# IC_LPDDR4.net
KiCad netlist of a schematic drawn in Altium Designer
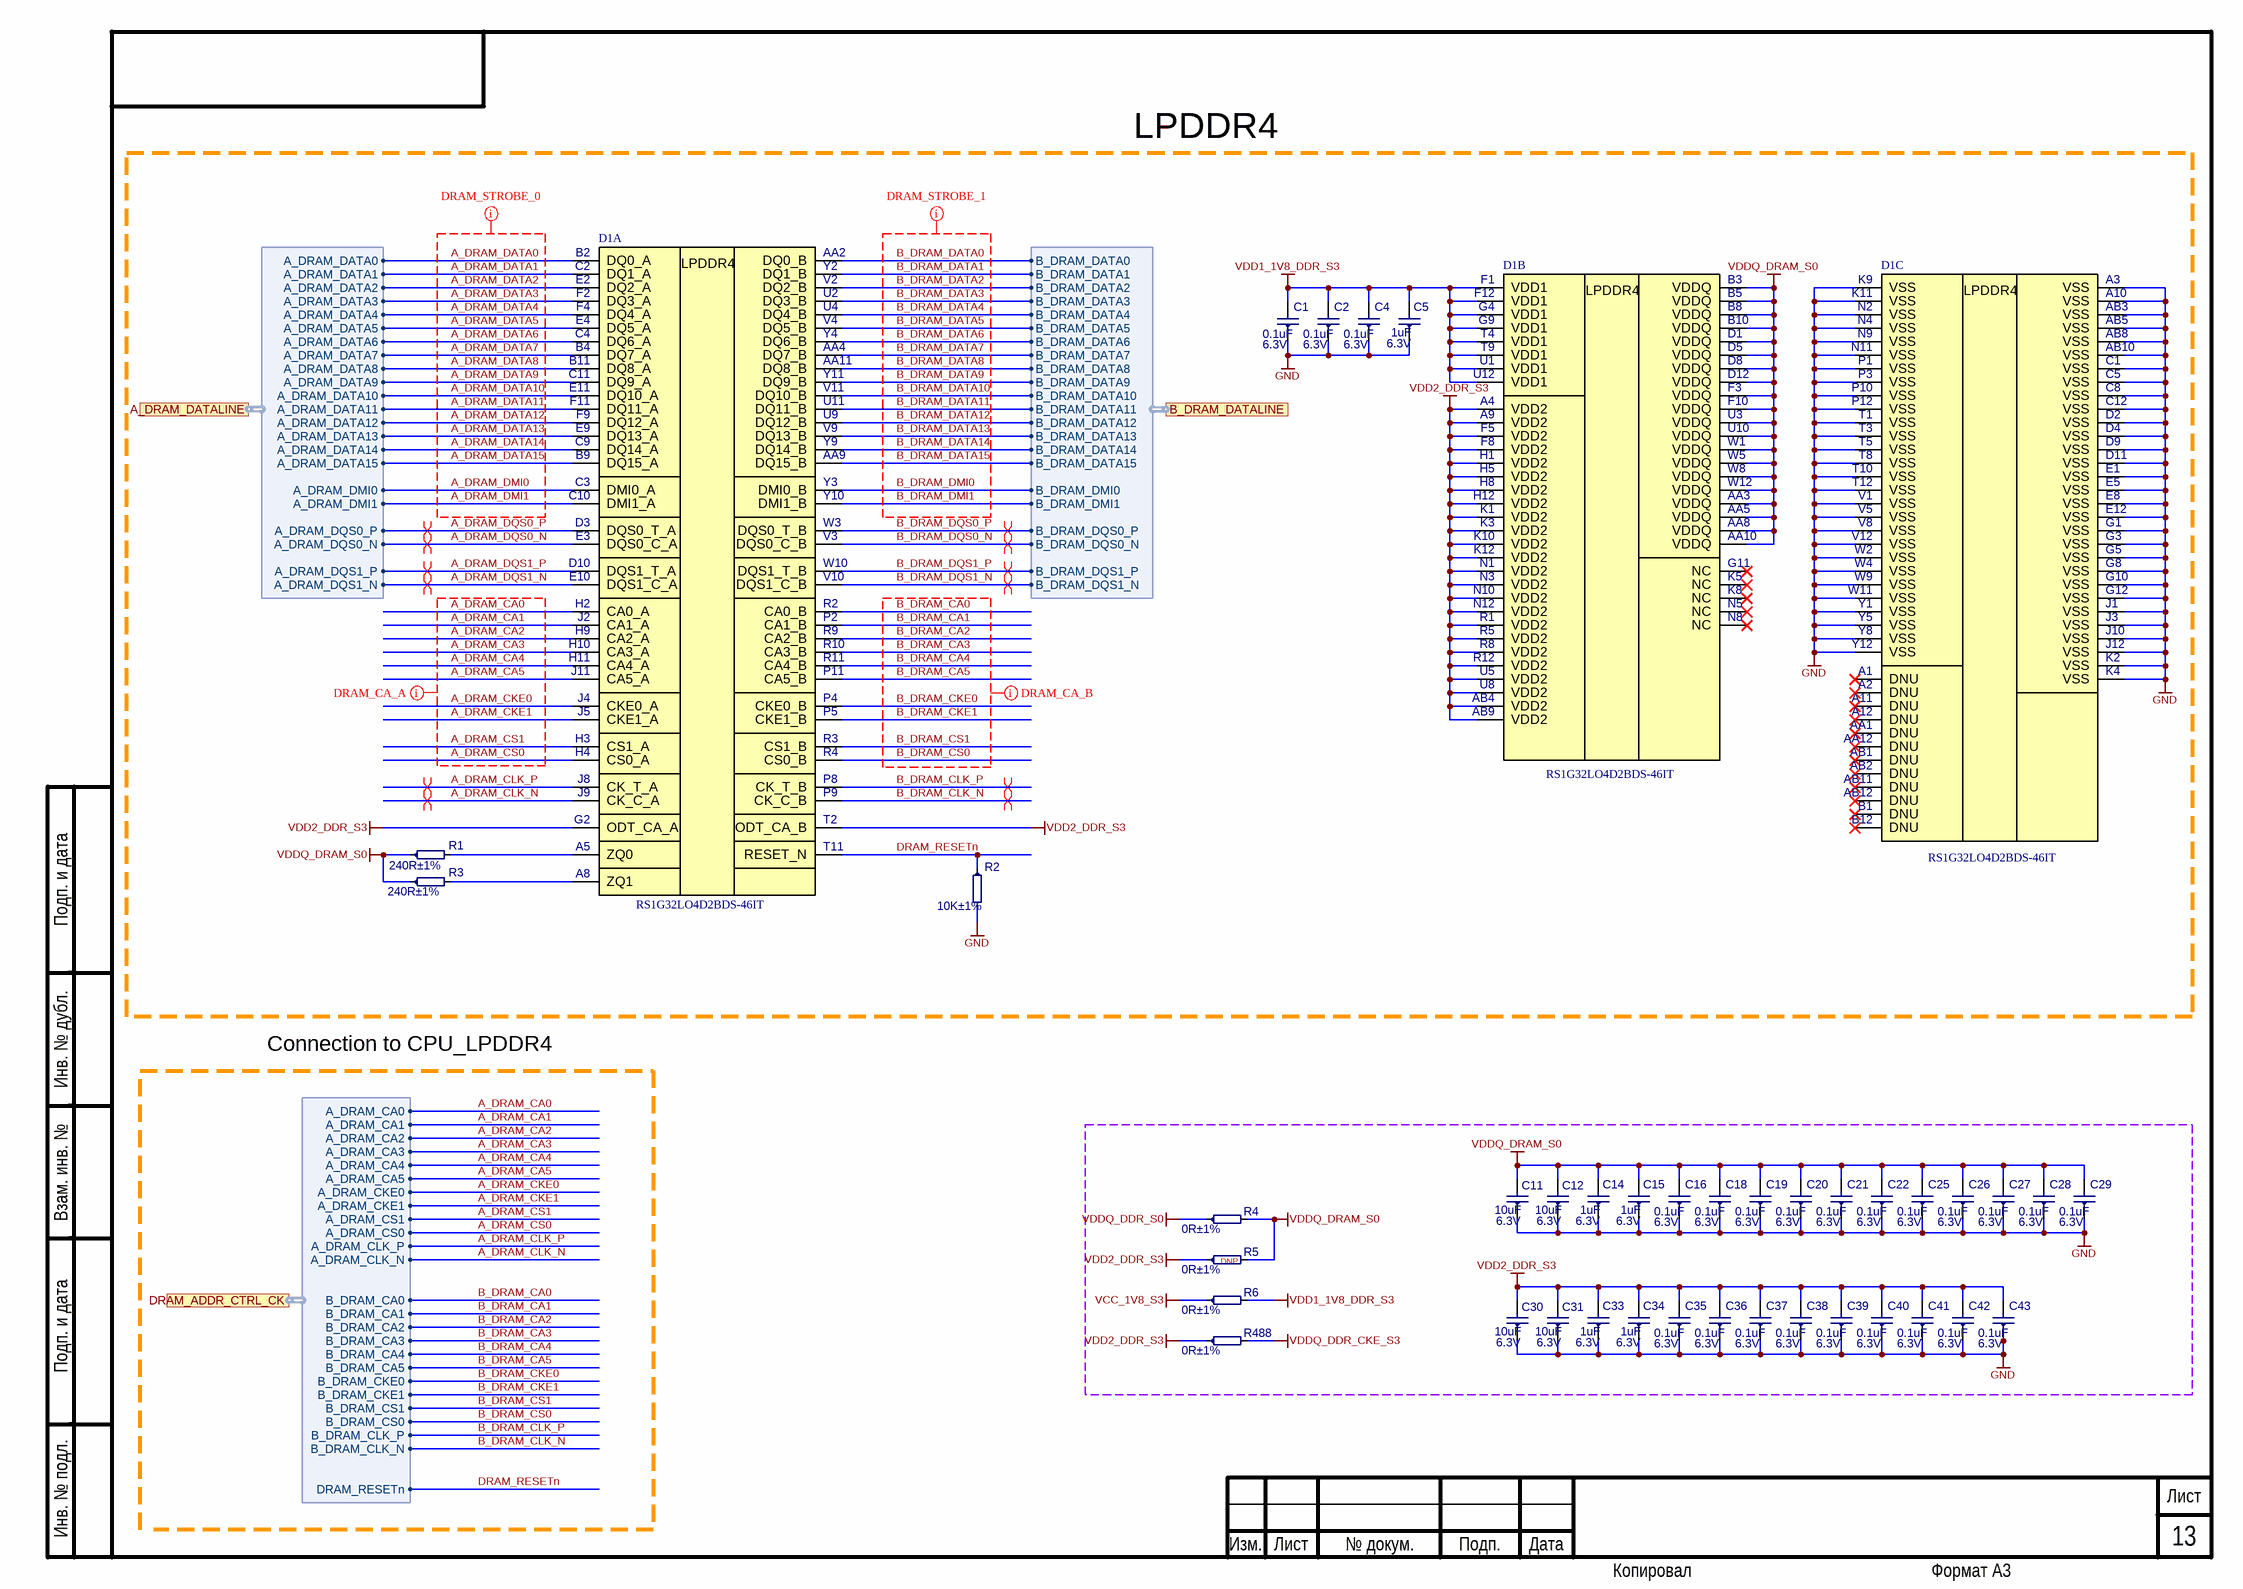
[diagram p0: IC_LPDDR4.SchDoc]

(export (version "E")
  (design (tool "Eeschema 10.0.6"))
  (components
    (comp (ref "C1")
      (value "0.1uF")
      (footprint "C0201")
      (fields
        (field (name "VOLTAGE") "6.3V")
        (field (name "PART NUMBER") "0201-X5R-6.3V-0.1uF±10%")
        (field (name "TOLERANCE") "10%")
        (field (name "MANUFACTURER") "Yageo")
      )
      (libsource (lib "ATB") (part "C"))
    )
    (comp (ref "C2")
      (value "0.1uF")
      (footprint "C0201")
      (fields
        (field (name "VOLTAGE") "6.3V")
        (field (name "PART NUMBER") "0201-X5R-6.3V-0.1uF±10%")
        (field (name "TOLERANCE") "10%")
        (field (name "MANUFACTURER") "Yageo")
      )
      (libsource (lib "ATB") (part "C"))
    )
    (comp (ref "C4")
      (value "0.1uF")
      (footprint "C0201")
      (fields
        (field (name "VOLTAGE") "6.3V")
        (field (name "PART NUMBER") "0201-X5R-6.3V-0.1uF±10%")
        (field (name "TOLERANCE") "10%")
        (field (name "MANUFACTURER") "Yageo")
      )
      (libsource (lib "ATB") (part "C"))
    )
    (comp (ref "C5")
      (value "1uF")
      (footprint "C0201")
      (fields
        (field (name "VOLTAGE") "6.3V")
        (field (name "PART NUMBER") "0201-X5R-6.3V-1uF±20%")
        (field (name "TOLERANCE") "20%")
        (field (name "MANUFACTURER") "Murata Electronics")
      )
      (libsource (lib "ATB") (part "C"))
    )
    (comp (ref "C11")
      (value "10uF")
      (footprint "C0402")
      (fields
        (field (name "VOLTAGE") "6.3V")
        (field (name "PART NUMBER") "0402-X5R-6.3V-10uF±20%")
        (field (name "TOLERANCE") "20%")
        (field (name "MANUFACTURER") "Yageo")
      )
      (libsource (lib "ATB") (part "C"))
    )
    (comp (ref "C12")
      (value "10uF")
      (footprint "C0402")
      (fields
        (field (name "VOLTAGE") "6.3V")
        (field (name "PART NUMBER") "0402-X5R-6.3V-10uF±20%")
        (field (name "TOLERANCE") "20%")
        (field (name "MANUFACTURER") "Yageo")
      )
      (libsource (lib "ATB") (part "C"))
    )
    (comp (ref "C14")
      (value "1uF")
      (footprint "C0201")
      (fields
        (field (name "VOLTAGE") "6.3V")
        (field (name "PART NUMBER") "0201-X5R-6.3V-1uF±20%")
        (field (name "TOLERANCE") "20%")
        (field (name "MANUFACTURER") "Murata Electronics")
      )
      (libsource (lib "ATB") (part "C"))
    )
    (comp (ref "C15")
      (value "1uF")
      (footprint "C0201")
      (fields
        (field (name "VOLTAGE") "6.3V")
        (field (name "PART NUMBER") "0201-X5R-6.3V-1uF±20%")
        (field (name "TOLERANCE") "20%")
        (field (name "MANUFACTURER") "Murata Electronics")
      )
      (libsource (lib "ATB") (part "C"))
    )
    (comp (ref "C16")
      (value "0.1uF")
      (footprint "C0201")
      (fields
        (field (name "VOLTAGE") "6.3V")
        (field (name "PART NUMBER") "0201-X5R-6.3V-0.1uF±10%")
        (field (name "TOLERANCE") "10%")
        (field (name "MANUFACTURER") "Yageo")
      )
      (libsource (lib "ATB") (part "C"))
    )
    (comp (ref "C18")
      (value "0.1uF")
      (footprint "C0201")
      (fields
        (field (name "VOLTAGE") "6.3V")
        (field (name "PART NUMBER") "0201-X5R-6.3V-0.1uF±10%")
        (field (name "TOLERANCE") "10%")
        (field (name "MANUFACTURER") "Yageo")
      )
      (libsource (lib "ATB") (part "C"))
    )
    (comp (ref "C19")
      (value "0.1uF")
      (footprint "C0201")
      (fields
        (field (name "VOLTAGE") "6.3V")
        (field (name "PART NUMBER") "0201-X5R-6.3V-0.1uF±10%")
        (field (name "TOLERANCE") "10%")
        (field (name "MANUFACTURER") "Yageo")
      )
      (libsource (lib "ATB") (part "C"))
    )
    (comp (ref "C20")
      (value "0.1uF")
      (footprint "C0201")
      (fields
        (field (name "VOLTAGE") "6.3V")
        (field (name "PART NUMBER") "0201-X5R-6.3V-0.1uF±10%")
        (field (name "TOLERANCE") "10%")
        (field (name "MANUFACTURER") "Yageo")
      )
      (libsource (lib "ATB") (part "C"))
    )
    (comp (ref "C21")
      (value "0.1uF")
      (footprint "C0201")
      (fields
        (field (name "VOLTAGE") "6.3V")
        (field (name "PART NUMBER") "0201-X5R-6.3V-0.1uF±10%")
        (field (name "TOLERANCE") "10%")
        (field (name "MANUFACTURER") "Yageo")
      )
      (libsource (lib "ATB") (part "C"))
    )
    (comp (ref "C22")
      (value "0.1uF")
      (footprint "C0201")
      (fields
        (field (name "VOLTAGE") "6.3V")
        (field (name "PART NUMBER") "0201-X5R-6.3V-0.1uF±10%")
        (field (name "TOLERANCE") "10%")
        (field (name "MANUFACTURER") "Yageo")
      )
      (libsource (lib "ATB") (part "C"))
    )
    (comp (ref "C25")
      (value "0.1uF")
      (footprint "C0201")
      (fields
        (field (name "VOLTAGE") "6.3V")
        (field (name "PART NUMBER") "0201-X5R-6.3V-0.1uF±10%")
        (field (name "TOLERANCE") "10%")
        (field (name "MANUFACTURER") "Yageo")
      )
      (libsource (lib "ATB") (part "C"))
    )
    (comp (ref "C26")
      (value "0.1uF")
      (footprint "C0201")
      (fields
        (field (name "VOLTAGE") "6.3V")
        (field (name "PART NUMBER") "0201-X5R-6.3V-0.1uF±10%")
        (field (name "TOLERANCE") "10%")
        (field (name "MANUFACTURER") "Yageo")
      )
      (libsource (lib "ATB") (part "C"))
    )
    (comp (ref "C27")
      (value "0.1uF")
      (footprint "C0201")
      (fields
        (field (name "VOLTAGE") "6.3V")
        (field (name "PART NUMBER") "0201-X5R-6.3V-0.1uF±10%")
        (field (name "TOLERANCE") "10%")
        (field (name "MANUFACTURER") "Yageo")
      )
      (libsource (lib "ATB") (part "C"))
    )
    (comp (ref "C28")
      (value "0.1uF")
      (footprint "C0201")
      (fields
        (field (name "VOLTAGE") "6.3V")
        (field (name "PART NUMBER") "0201-X5R-6.3V-0.1uF±10%")
        (field (name "TOLERANCE") "10%")
        (field (name "MANUFACTURER") "Yageo")
      )
      (libsource (lib "ATB") (part "C"))
    )
    (comp (ref "C29")
      (value "0.1uF")
      (footprint "C0201")
      (fields
        (field (name "VOLTAGE") "6.3V")
        (field (name "PART NUMBER") "0201-X5R-6.3V-0.1uF±10%")
        (field (name "TOLERANCE") "10%")
        (field (name "MANUFACTURER") "Yageo")
      )
      (libsource (lib "ATB") (part "C"))
    )
    (comp (ref "C30")
      (value "10uF")
      (footprint "C0402")
      (fields
        (field (name "VOLTAGE") "6.3V")
        (field (name "PART NUMBER") "0402-X5R-6.3V-10uF±20%")
        (field (name "TOLERANCE") "20%")
        (field (name "MANUFACTURER") "Yageo")
      )
      (libsource (lib "ATB") (part "C"))
    )
    (comp (ref "C31")
      (value "10uF")
      (footprint "C0402")
      (fields
        (field (name "VOLTAGE") "6.3V")
        (field (name "PART NUMBER") "0402-X5R-6.3V-10uF±20%")
        (field (name "TOLERANCE") "20%")
        (field (name "MANUFACTURER") "Yageo")
      )
      (libsource (lib "ATB") (part "C"))
    )
    (comp (ref "C33")
      (value "1uF")
      (footprint "C0201")
      (fields
        (field (name "VOLTAGE") "6.3V")
        (field (name "PART NUMBER") "0201-X5R-6.3V-1uF±20%")
        (field (name "TOLERANCE") "20%")
        (field (name "MANUFACTURER") "Murata Electronics")
      )
      (libsource (lib "ATB") (part "C"))
    )
    (comp (ref "C34")
      (value "1uF")
      (footprint "C0201")
      (fields
        (field (name "VOLTAGE") "6.3V")
        (field (name "PART NUMBER") "0201-X5R-6.3V-1uF±20%")
        (field (name "TOLERANCE") "20%")
        (field (name "MANUFACTURER") "Murata Electronics")
      )
      (libsource (lib "ATB") (part "C"))
    )
    (comp (ref "C35")
      (value "0.1uF")
      (footprint "C0201")
      (fields
        (field (name "VOLTAGE") "6.3V")
        (field (name "PART NUMBER") "0201-X5R-6.3V-0.1uF±10%")
        (field (name "TOLERANCE") "10%")
        (field (name "MANUFACTURER") "Yageo")
      )
      (libsource (lib "ATB") (part "C"))
    )
    (comp (ref "C36")
      (value "0.1uF")
      (footprint "C0201")
      (fields
        (field (name "VOLTAGE") "6.3V")
        (field (name "PART NUMBER") "0201-X5R-6.3V-0.1uF±10%")
        (field (name "TOLERANCE") "10%")
        (field (name "MANUFACTURER") "Yageo")
      )
      (libsource (lib "ATB") (part "C"))
    )
    (comp (ref "C37")
      (value "0.1uF")
      (footprint "C0201")
      (fields
        (field (name "VOLTAGE") "6.3V")
        (field (name "PART NUMBER") "0201-X5R-6.3V-0.1uF±10%")
        (field (name "TOLERANCE") "10%")
        (field (name "MANUFACTURER") "Yageo")
      )
      (libsource (lib "ATB") (part "C"))
    )
    (comp (ref "C38")
      (value "0.1uF")
      (footprint "C0201")
      (fields
        (field (name "VOLTAGE") "6.3V")
        (field (name "PART NUMBER") "0201-X5R-6.3V-0.1uF±10%")
        (field (name "TOLERANCE") "10%")
        (field (name "MANUFACTURER") "Yageo")
      )
      (libsource (lib "ATB") (part "C"))
    )
    (comp (ref "C39")
      (value "0.1uF")
      (footprint "C0201")
      (fields
        (field (name "VOLTAGE") "6.3V")
        (field (name "PART NUMBER") "0201-X5R-6.3V-0.1uF±10%")
        (field (name "TOLERANCE") "10%")
        (field (name "MANUFACTURER") "Yageo")
      )
      (libsource (lib "ATB") (part "C"))
    )
    (comp (ref "C40")
      (value "0.1uF")
      (footprint "C0201")
      (fields
        (field (name "VOLTAGE") "6.3V")
        (field (name "PART NUMBER") "0201-X5R-6.3V-0.1uF±10%")
        (field (name "TOLERANCE") "10%")
        (field (name "MANUFACTURER") "Yageo")
      )
      (libsource (lib "ATB") (part "C"))
    )
    (comp (ref "C41")
      (value "0.1uF")
      (footprint "C0201")
      (fields
        (field (name "VOLTAGE") "6.3V")
        (field (name "PART NUMBER") "0201-X5R-6.3V-0.1uF±10%")
        (field (name "TOLERANCE") "10%")
        (field (name "MANUFACTURER") "Yageo")
      )
      (libsource (lib "ATB") (part "C"))
    )
    (comp (ref "C42")
      (value "0.1uF")
      (footprint "C0201")
      (fields
        (field (name "VOLTAGE") "6.3V")
        (field (name "PART NUMBER") "0201-X5R-6.3V-0.1uF±10%")
        (field (name "TOLERANCE") "10%")
        (field (name "MANUFACTURER") "Yageo")
      )
      (libsource (lib "ATB") (part "C"))
    )
    (comp (ref "C43")
      (value "0.1uF")
      (footprint "C0201")
      (fields
        (field (name "VOLTAGE") "6.3V")
        (field (name "PART NUMBER") "0201-X5R-6.3V-0.1uF±10%")
        (field (name "TOLERANCE") "10%")
        (field (name "MANUFACTURER") "Yageo")
      )
      (libsource (lib "ATB") (part "C"))
    )
    (comp (ref "D1")
      (value "RS1G32LO4D2BDS-46IT")
      (footprint "RS1G32LO4D2BDS-46IT")
      (description "DDR4 SDRAM емкостью 32 Гбит с организацией 1024М x 32 бит")
      (fields (field (name "MANUFACTURER") "Rayson"))
      (libsource (lib "LIB_RK") (part "RS1G32LO4D2BDS-46IT"))
    )
    (comp (ref "R1")
      (value "240R±1%")
      (footprint "R0402")
      (fields
        (field (name "PART NUMBER") "0402-0.0625W-240R-100ppm±1%")
        (field (name "TOLERANCE") "1%")
        (field (name "MANUFACTURER") "Yageo")
      )
      (libsource (lib "ATB") (part "R"))
    )
    (comp (ref "R2")
      (value "10K±1%")
      (footprint "R0402")
      (description "Chip Resistor 0402 10kΩ ±1% 50V ±100ppm/℃ Thick Film")
      (fields (field (name "PART NUMBER") "0402-0.0625W-10K-100ppm±1%") (field (name "TOLERANCE") "1%"))
      (libsource (lib "ATB") (part "R"))
    )
    (comp (ref "R3")
      (value "240R±1%")
      (footprint "R0402")
      (fields
        (field (name "PART NUMBER") "0402-0.0625W-240R-100ppm±1%")
        (field (name "TOLERANCE") "1%")
        (field (name "MANUFACTURER") "Yageo")
      )
      (libsource (lib "ATB") (part "R"))
    )
    (comp (ref "R4")
      (value "0R±1%")
      (footprint "R0402")
      (description "Chip Resistor 0402 0Ω ±1% 50V ±100ppm/℃ Thick Film")
      (fields (field (name "PART NUMBER") "0402-0.0625W-0R-100ppm±1%") (field (name "TOLERANCE") "1%"))
      (libsource (lib "ATB") (part "R"))
    )
    (comp (ref "R5")
      (value "0R±1%")
      (footprint "R0402")
      (description "Chip Resistor 0402 0Ω ±1% 50V ±100ppm/℃ Thick Film")
      (fields (field (name "PART NUMBER") "0402-0.0625W-0R-100ppm±1%") (field (name "TOLERANCE") "1%"))
      (libsource (lib "ATB") (part "R"))
    )
    (comp (ref "R6")
      (value "0R±1%")
      (footprint "R0402")
      (description "Chip Resistor 0402 0Ω ±1% 50V ±100ppm/℃ Thick Film")
      (fields (field (name "PART NUMBER") "0402-0.0625W-0R-100ppm±1%") (field (name "TOLERANCE") "1%"))
      (libsource (lib "ATB") (part "R"))
    )
    (comp (ref "R488")
      (value "0R±1%")
      (footprint "R0402")
      (description "Chip Resistor 0402 0Ω ±1% 50V ±100ppm/℃ Thick Film")
      (fields (field (name "PART NUMBER") "0402-0.0625W-0R-100ppm±1%") (field (name "TOLERANCE") "1%"))
      (libsource (lib "ATB") (part "R"))
    )
  )
  (nets
    (net (code "4") (name "/A_DRAM_CA0") (class "Default")
      (node (ref "D1") (pin "H2") (pinfunction "CA0_A_H2") (pintype "passive"))
    )
    (net (code "5") (name "/A_DRAM_CA1") (class "Default")
      (node (ref "D1") (pin "J2") (pinfunction "CA1_A_J2") (pintype "passive"))
    )
    (net (code "6") (name "/A_DRAM_CA2") (class "Default")
      (node (ref "D1") (pin "H9") (pinfunction "CA2_A_H9") (pintype "passive"))
    )
    (net (code "7") (name "/A_DRAM_CA3") (class "Default")
      (node (ref "D1") (pin "H10") (pinfunction "CA3_A_H10") (pintype "passive"))
    )
    (net (code "8") (name "/A_DRAM_CA4") (class "Default")
      (node (ref "D1") (pin "H11") (pinfunction "CA4_A_H11") (pintype "passive"))
    )
    (net (code "9") (name "/A_DRAM_CA5") (class "Default")
      (node (ref "D1") (pin "J11") (pinfunction "CA5_A_J11") (pintype "passive"))
    )
    (net (code "10") (name "/A_DRAM_CKE0") (class "Default")
      (node (ref "D1") (pin "J4") (pinfunction "CKE0_A_J4") (pintype "passive"))
    )
    (net (code "11") (name "/A_DRAM_CKE1") (class "Default")
      (node (ref "D1") (pin "J5") (pinfunction "CKE1_A_J5") (pintype "passive"))
    )
    (net (code "12") (name "/A_DRAM_CLK_N") (class "Default")
      (node (ref "D1") (pin "J9") (pinfunction "CK_C_A_J9") (pintype "passive"))
    )
    (net (code "13") (name "/A_DRAM_CLK_P") (class "Default")
      (node (ref "D1") (pin "J8") (pinfunction "CK_T_A_J8") (pintype "passive"))
    )
    (net (code "14") (name "/A_DRAM_CS0") (class "Default")
      (node (ref "D1") (pin "H4") (pinfunction "CS0_A_H4") (pintype "passive"))
    )
    (net (code "15") (name "/A_DRAM_CS1") (class "Default")
      (node (ref "D1") (pin "H3") (pinfunction "CS1_A_H3") (pintype "passive"))
    )
    (net (code "16") (name "/A_DRAM_DATA0") (class "Default")
      (node (ref "D1") (pin "B2") (pinfunction "DQ0_A_B2") (pintype "passive"))
    )
    (net (code "17") (name "/A_DRAM_DATA1") (class "Default")
      (node (ref "D1") (pin "C2") (pinfunction "DQ1_A_C2") (pintype "passive"))
    )
    (net (code "18") (name "/A_DRAM_DATA2") (class "Default")
      (node (ref "D1") (pin "E2") (pinfunction "DQ2_A_E2") (pintype "passive"))
    )
    (net (code "19") (name "/A_DRAM_DATA3") (class "Default")
      (node (ref "D1") (pin "F2") (pinfunction "DQ3_A_F2") (pintype "passive"))
    )
    (net (code "20") (name "/A_DRAM_DATA4") (class "Default")
      (node (ref "D1") (pin "F4") (pinfunction "DQ4_A_F4") (pintype "passive"))
    )
    (net (code "21") (name "/A_DRAM_DATA5") (class "Default")
      (node (ref "D1") (pin "E4") (pinfunction "DQ5_A_E4") (pintype "passive"))
    )
    (net (code "22") (name "/A_DRAM_DATA6") (class "Default")
      (node (ref "D1") (pin "C4") (pinfunction "DQ6_A_C4") (pintype "passive"))
    )
    (net (code "23") (name "/A_DRAM_DATA7") (class "Default")
      (node (ref "D1") (pin "B4") (pinfunction "DQ7_A_B4") (pintype "passive"))
    )
    (net (code "24") (name "/A_DRAM_DATA8") (class "Default")
      (node (ref "D1") (pin "B11") (pinfunction "DQ8_A_B11") (pintype "passive"))
    )
    (net (code "25") (name "/A_DRAM_DATA9") (class "Default")
      (node (ref "D1") (pin "C11") (pinfunction "DQ9_A_C11") (pintype "passive"))
    )
    (net (code "26") (name "/A_DRAM_DATA10") (class "Default")
      (node (ref "D1") (pin "E11") (pinfunction "DQ10_A_E11") (pintype "passive"))
    )
    (net (code "27") (name "/A_DRAM_DATA11") (class "Default")
      (node (ref "D1") (pin "F11") (pinfunction "DQ11_A_F11") (pintype "passive"))
    )
    (net (code "28") (name "/A_DRAM_DATA12") (class "Default")
      (node (ref "D1") (pin "F9") (pinfunction "DQ12_A_F9") (pintype "passive"))
    )
    (net (code "29") (name "/A_DRAM_DATA13") (class "Default")
      (node (ref "D1") (pin "E9") (pinfunction "DQ13_A_E9") (pintype "passive"))
    )
    (net (code "30") (name "/A_DRAM_DATA14") (class "Default")
      (node (ref "D1") (pin "C9") (pinfunction "DQ14_A_C9") (pintype "passive"))
    )
    (net (code "31") (name "/A_DRAM_DATA15") (class "Default")
      (node (ref "D1") (pin "B9") (pinfunction "DQ15_A_B9") (pintype "passive"))
    )
    (net (code "32") (name "/A_DRAM_DMI0") (class "Default")
      (node (ref "D1") (pin "C3") (pinfunction "DMI0_A_C3") (pintype "passive"))
    )
    (net (code "33") (name "/A_DRAM_DMI1") (class "Default")
      (node (ref "D1") (pin "C10") (pinfunction "DMI1_A_C10") (pintype "passive"))
    )
    (net (code "34") (name "/A_DRAM_DQS0_N") (class "Default")
      (node (ref "D1") (pin "E3") (pinfunction "DQS0_C_A_E3") (pintype "passive"))
    )
    (net (code "35") (name "/A_DRAM_DQS0_P") (class "Default")
      (node (ref "D1") (pin "D3") (pinfunction "DQS0_T_A_D3") (pintype "passive"))
    )
    (net (code "36") (name "/A_DRAM_DQS1_N") (class "Default")
      (node (ref "D1") (pin "E10") (pinfunction "DQS1_C_A_E10") (pintype "passive"))
    )
    (net (code "37") (name "/A_DRAM_DQS1_P") (class "Default")
      (node (ref "D1") (pin "D10") (pinfunction "DQS1_T_A_D10") (pintype "passive"))
    )
    (net (code "38") (name "/B_DRAM_CA0") (class "Default")
      (node (ref "D1") (pin "R2") (pinfunction "CA0_B_R2") (pintype "passive"))
    )
    (net (code "39") (name "/B_DRAM_CA1") (class "Default")
      (node (ref "D1") (pin "P2") (pinfunction "CA1_B_P2") (pintype "passive"))
    )
    (net (code "40") (name "/B_DRAM_CA2") (class "Default")
      (node (ref "D1") (pin "R9") (pinfunction "CA2_B_R9") (pintype "passive"))
    )
    (net (code "41") (name "/B_DRAM_CA3") (class "Default")
      (node (ref "D1") (pin "R10") (pinfunction "CA3_B_R10") (pintype "passive"))
    )
    (net (code "42") (name "/B_DRAM_CA4") (class "Default")
      (node (ref "D1") (pin "R11") (pinfunction "CA4_B_R11") (pintype "passive"))
    )
    (net (code "43") (name "/B_DRAM_CA5") (class "Default")
      (node (ref "D1") (pin "P11") (pinfunction "CA5_B_P11") (pintype "passive"))
    )
    (net (code "44") (name "/B_DRAM_CKE0") (class "Default")
      (node (ref "D1") (pin "P4") (pinfunction "CKE0_B_P4") (pintype "passive"))
    )
    (net (code "45") (name "/B_DRAM_CKE1") (class "Default")
      (node (ref "D1") (pin "P5") (pinfunction "CKE1_B_P5") (pintype "passive"))
    )
    (net (code "46") (name "/B_DRAM_CLK_N") (class "Default")
      (node (ref "D1") (pin "P9") (pinfunction "CK_C_B_P9") (pintype "passive"))
    )
    (net (code "47") (name "/B_DRAM_CLK_P") (class "Default")
      (node (ref "D1") (pin "P8") (pinfunction "CK_T_B_P8") (pintype "passive"))
    )
    (net (code "48") (name "/B_DRAM_CS0") (class "Default")
      (node (ref "D1") (pin "R4") (pinfunction "CS0_B_R4") (pintype "passive"))
    )
    (net (code "49") (name "/B_DRAM_CS1") (class "Default")
      (node (ref "D1") (pin "R3") (pinfunction "CS1_B_R3") (pintype "passive"))
    )
    (net (code "50") (name "/B_DRAM_DATA0") (class "Default")
      (node (ref "D1") (pin "AA2") (pinfunction "DQ0_B_AA2") (pintype "passive"))
    )
    (net (code "51") (name "/B_DRAM_DATA1") (class "Default")
      (node (ref "D1") (pin "Y2") (pinfunction "DQ1_B_Y2") (pintype "passive"))
    )
    (net (code "52") (name "/B_DRAM_DATA2") (class "Default")
      (node (ref "D1") (pin "V2") (pinfunction "DQ2_B_V2") (pintype "passive"))
    )
    (net (code "53") (name "/B_DRAM_DATA3") (class "Default")
      (node (ref "D1") (pin "U2") (pinfunction "DQ3_B_U2") (pintype "passive"))
    )
    (net (code "54") (name "/B_DRAM_DATA4") (class "Default")
      (node (ref "D1") (pin "U4") (pinfunction "DQ4_B_U4") (pintype "passive"))
    )
    (net (code "55") (name "/B_DRAM_DATA5") (class "Default")
      (node (ref "D1") (pin "V4") (pinfunction "DQ5_B_V4") (pintype "passive"))
    )
    (net (code "56") (name "/B_DRAM_DATA6") (class "Default")
      (node (ref "D1") (pin "Y4") (pinfunction "DQ6_B_Y4") (pintype "passive"))
    )
    (net (code "57") (name "/B_DRAM_DATA7") (class "Default")
      (node (ref "D1") (pin "AA4") (pinfunction "DQ7_B_AA4") (pintype "passive"))
    )
    (net (code "58") (name "/B_DRAM_DATA8") (class "Default")
      (node (ref "D1") (pin "AA11") (pinfunction "DQ8_B_AA11") (pintype "passive"))
    )
    (net (code "59") (name "/B_DRAM_DATA9") (class "Default")
      (node (ref "D1") (pin "Y11") (pinfunction "DQ9_B_Y11") (pintype "passive"))
    )
    (net (code "60") (name "/B_DRAM_DATA10") (class "Default")
      (node (ref "D1") (pin "V11") (pinfunction "DQ10_B_V11") (pintype "passive"))
    )
    (net (code "61") (name "/B_DRAM_DATA11") (class "Default")
      (node (ref "D1") (pin "U11") (pinfunction "DQ11_B_U11") (pintype "passive"))
    )
    (net (code "62") (name "/B_DRAM_DATA12") (class "Default")
      (node (ref "D1") (pin "U9") (pinfunction "DQ12_B_U9") (pintype "passive"))
    )
    (net (code "63") (name "/B_DRAM_DATA13") (class "Default")
      (node (ref "D1") (pin "V9") (pinfunction "DQ13_B_V9") (pintype "passive"))
    )
    (net (code "64") (name "/B_DRAM_DATA14") (class "Default")
      (node (ref "D1") (pin "Y9") (pinfunction "DQ14_B_Y9") (pintype "passive"))
    )
    (net (code "65") (name "/B_DRAM_DATA15") (class "Default")
      (node (ref "D1") (pin "AA9") (pinfunction "DQ15_B_AA9") (pintype "passive"))
    )
    (net (code "66") (name "/B_DRAM_DMI0") (class "Default")
      (node (ref "D1") (pin "Y3") (pinfunction "DMI0_B_Y3") (pintype "passive"))
    )
    (net (code "67") (name "/B_DRAM_DMI1") (class "Default")
      (node (ref "D1") (pin "Y10") (pinfunction "DMI1_B_Y10") (pintype "passive"))
    )
    (net (code "68") (name "/B_DRAM_DQS0_N") (class "Default")
      (node (ref "D1") (pin "V3") (pinfunction "DQS0_C_B_V3") (pintype "passive"))
    )
    (net (code "69") (name "/B_DRAM_DQS0_P") (class "Default")
      (node (ref "D1") (pin "W3") (pinfunction "DQS0_T_B_W3") (pintype "passive"))
    )
    (net (code "70") (name "/B_DRAM_DQS1_N") (class "Default")
      (node (ref "D1") (pin "V10") (pinfunction "DQS1_C_B_V10") (pintype "passive"))
    )
    (net (code "71") (name "/B_DRAM_DQS1_P") (class "Default")
      (node (ref "D1") (pin "W10") (pinfunction "DQS1_T_B_W10") (pintype "passive"))
    )
    (net (code "72") (name "/DRAM_RESETn") (class "Default")
      (node (ref "D1") (pin "T11") (pinfunction "RESET_N_T11") (pintype "passive"))
      (node (ref "R2") (pin "1") (pinfunction "1_1") (pintype "passive"))
    )
    (net (code "76") (name "GND") (class "Default")
      (node (ref "C1") (pin "1") (pinfunction "1_1") (pintype "passive"))
      (node (ref "C11") (pin "1") (pinfunction "1_1") (pintype "passive"))
      (node (ref "C12") (pin "1") (pinfunction "1_1") (pintype "passive"))
      (node (ref "C14") (pin "1") (pinfunction "1_1") (pintype "passive"))
      (node (ref "C15") (pin "1") (pinfunction "1_1") (pintype "passive"))
      (node (ref "C16") (pin "1") (pinfunction "1_1") (pintype "passive"))
      (node (ref "C18") (pin "1") (pinfunction "1_1") (pintype "passive"))
      (node (ref "C19") (pin "1") (pinfunction "1_1") (pintype "passive"))
      (node (ref "C2") (pin "1") (pinfunction "1_1") (pintype "passive"))
      (node (ref "C20") (pin "1") (pinfunction "1_1") (pintype "passive"))
      (node (ref "C21") (pin "1") (pinfunction "1_1") (pintype "passive"))
      (node (ref "C22") (pin "1") (pinfunction "1_1") (pintype "passive"))
      (node (ref "C25") (pin "1") (pinfunction "1_1") (pintype "passive"))
      (node (ref "C26") (pin "1") (pinfunction "1_1") (pintype "passive"))
      (node (ref "C27") (pin "1") (pinfunction "1_1") (pintype "passive"))
      (node (ref "C28") (pin "1") (pinfunction "1_1") (pintype "passive"))
      (node (ref "C29") (pin "1") (pinfunction "1_1") (pintype "passive"))
      (node (ref "C30") (pin "1") (pinfunction "1_1") (pintype "passive"))
      (node (ref "C31") (pin "1") (pinfunction "1_1") (pintype "passive"))
      (node (ref "C33") (pin "1") (pinfunction "1_1") (pintype "passive"))
      (node (ref "C34") (pin "1") (pinfunction "1_1") (pintype "passive"))
      (node (ref "C35") (pin "1") (pinfunction "1_1") (pintype "passive"))
      (node (ref "C36") (pin "1") (pinfunction "1_1") (pintype "passive"))
      (node (ref "C37") (pin "1") (pinfunction "1_1") (pintype "passive"))
      (node (ref "C38") (pin "1") (pinfunction "1_1") (pintype "passive"))
      (node (ref "C39") (pin "1") (pinfunction "1_1") (pintype "passive"))
      (node (ref "C4") (pin "1") (pinfunction "1_1") (pintype "passive"))
      (node (ref "C40") (pin "1") (pinfunction "1_1") (pintype "passive"))
      (node (ref "C41") (pin "1") (pinfunction "1_1") (pintype "passive"))
      (node (ref "C42") (pin "1") (pinfunction "1_1") (pintype "passive"))
      (node (ref "C43") (pin "1") (pinfunction "1_1") (pintype "passive"))
      (node (ref "C5") (pin "1") (pinfunction "1_1") (pintype "passive"))
      (node (ref "D1") (pin "A10") (pinfunction "VSS_A10") (pintype "passive"))
      (node (ref "D1") (pin "A3") (pinfunction "VSS_A3") (pintype "passive"))
      (node (ref "D1") (pin "AB10") (pinfunction "VSS_AB10") (pintype "passive"))
      (node (ref "D1") (pin "AB3") (pinfunction "VSS_AB3") (pintype "passive"))
      (node (ref "D1") (pin "AB5") (pinfunction "VSS_AB5") (pintype "passive"))
      (node (ref "D1") (pin "AB8") (pinfunction "VSS_AB8") (pintype "passive"))
      (node (ref "D1") (pin "C1") (pinfunction "VSS_C1") (pintype "passive"))
      (node (ref "D1") (pin "C12") (pinfunction "VSS_C12") (pintype "passive"))
      (node (ref "D1") (pin "C5") (pinfunction "VSS_C5") (pintype "passive"))
      (node (ref "D1") (pin "C8") (pinfunction "VSS_C8") (pintype "passive"))
      (node (ref "D1") (pin "D11") (pinfunction "VSS_D11") (pintype "passive"))
      (node (ref "D1") (pin "D2") (pinfunction "VSS_D2") (pintype "passive"))
      (node (ref "D1") (pin "D4") (pinfunction "VSS_D4") (pintype "passive"))
      (node (ref "D1") (pin "D9") (pinfunction "VSS_D9") (pintype "passive"))
      (node (ref "D1") (pin "E1") (pinfunction "VSS_E1") (pintype "passive"))
      (node (ref "D1") (pin "E12") (pinfunction "VSS_E12") (pintype "passive"))
      (node (ref "D1") (pin "E5") (pinfunction "VSS_E5") (pintype "passive"))
      (node (ref "D1") (pin "E8") (pinfunction "VSS_E8") (pintype "passive"))
      (node (ref "D1") (pin "G1") (pinfunction "VSS_G1") (pintype "passive"))
      (node (ref "D1") (pin "G10") (pinfunction "VSS_G10") (pintype "passive"))
      (node (ref "D1") (pin "G12") (pinfunction "VSS_G12") (pintype "passive"))
      (node (ref "D1") (pin "G3") (pinfunction "VSS_G3") (pintype "passive"))
      (node (ref "D1") (pin "G5") (pinfunction "VSS_G5") (pintype "passive"))
      (node (ref "D1") (pin "G8") (pinfunction "VSS_G8") (pintype "passive"))
      (node (ref "D1") (pin "J1") (pinfunction "VSS_J1") (pintype "passive"))
      (node (ref "D1") (pin "J10") (pinfunction "VSS_J10") (pintype "passive"))
      (node (ref "D1") (pin "J12") (pinfunction "VSS_J12") (pintype "passive"))
      (node (ref "D1") (pin "J3") (pinfunction "VSS_J3") (pintype "passive"))
      (node (ref "D1") (pin "K11") (pinfunction "VSS_K11") (pintype "passive"))
      (node (ref "D1") (pin "K2") (pinfunction "VSS_K2") (pintype "passive"))
      (node (ref "D1") (pin "K4") (pinfunction "VSS_K4") (pintype "passive"))
      (node (ref "D1") (pin "K9") (pinfunction "VSS_K9") (pintype "passive"))
      (node (ref "D1") (pin "N11") (pinfunction "VSS_N11") (pintype "passive"))
      (node (ref "D1") (pin "N2") (pinfunction "VSS_N2") (pintype "passive"))
      (node (ref "D1") (pin "N4") (pinfunction "VSS_N4") (pintype "passive"))
      (node (ref "D1") (pin "N9") (pinfunction "VSS_N9") (pintype "passive"))
      (node (ref "D1") (pin "P1") (pinfunction "VSS_P1") (pintype "passive"))
      (node (ref "D1") (pin "P10") (pinfunction "VSS_P10") (pintype "passive"))
      (node (ref "D1") (pin "P12") (pinfunction "VSS_P12") (pintype "passive"))
      (node (ref "D1") (pin "P3") (pinfunction "VSS_P3") (pintype "passive"))
      (node (ref "D1") (pin "T1") (pinfunction "VSS_T1") (pintype "passive"))
      (node (ref "D1") (pin "T10") (pinfunction "VSS_T10") (pintype "passive"))
      (node (ref "D1") (pin "T12") (pinfunction "VSS_T12") (pintype "passive"))
      (node (ref "D1") (pin "T3") (pinfunction "VSS_T3") (pintype "passive"))
      (node (ref "D1") (pin "T5") (pinfunction "VSS_T5") (pintype "passive"))
      (node (ref "D1") (pin "T8") (pinfunction "VSS_T8") (pintype "passive"))
      (node (ref "D1") (pin "V1") (pinfunction "VSS_V1") (pintype "passive"))
      (node (ref "D1") (pin "V12") (pinfunction "VSS_V12") (pintype "passive"))
      (node (ref "D1") (pin "V5") (pinfunction "VSS_V5") (pintype "passive"))
      (node (ref "D1") (pin "V8") (pinfunction "VSS_V8") (pintype "passive"))
      (node (ref "D1") (pin "W11") (pinfunction "VSS_W11") (pintype "passive"))
      (node (ref "D1") (pin "W2") (pinfunction "VSS_W2") (pintype "passive"))
      (node (ref "D1") (pin "W4") (pinfunction "VSS_W4") (pintype "passive"))
      (node (ref "D1") (pin "W9") (pinfunction "VSS_W9") (pintype "passive"))
      (node (ref "D1") (pin "Y1") (pinfunction "VSS_Y1") (pintype "passive"))
      (node (ref "D1") (pin "Y12") (pinfunction "VSS_Y12") (pintype "passive"))
      (node (ref "D1") (pin "Y5") (pinfunction "VSS_Y5") (pintype "passive"))
      (node (ref "D1") (pin "Y8") (pinfunction "VSS_Y8") (pintype "passive"))
      (node (ref "R2") (pin "2") (pinfunction "2_2") (pintype "passive"))
    )
    (net (code "77") (name "Net-(D1A-ZQ0)") (class "Default")
      (node (ref "D1") (pin "A5") (pinfunction "ZQ0_A5") (pintype "passive"))
      (node (ref "R1") (pin "2") (pinfunction "2_2") (pintype "passive"))
    )
    (net (code "78") (name "Net-(D1A-ZQ1)") (class "Default")
      (node (ref "D1") (pin "A8") (pinfunction "ZQ1_A8") (pintype "passive"))
      (node (ref "R3") (pin "2") (pinfunction "2_2") (pintype "passive"))
    )
    (net (code "79") (name "VCC_1V8_S3") (class "Default")
      (node (ref "R6") (pin "1") (pinfunction "1_1") (pintype "passive"))
    )
    (net (code "80") (name "VDD1_1V8_DDR_S3") (class "Default")
      (node (ref "C1") (pin "2") (pinfunction "2_2") (pintype "passive"))
      (node (ref "C2") (pin "2") (pinfunction "2_2") (pintype "passive"))
      (node (ref "C4") (pin "2") (pinfunction "2_2") (pintype "passive"))
      (node (ref "C5") (pin "2") (pinfunction "2_2") (pintype "passive"))
      (node (ref "D1") (pin "F1") (pinfunction "VDD1_F1") (pintype "passive"))
      (node (ref "D1") (pin "F12") (pinfunction "VDD1_F12") (pintype "passive"))
      (node (ref "D1") (pin "G4") (pinfunction "VDD1_G4") (pintype "passive"))
      (node (ref "D1") (pin "G9") (pinfunction "VDD1_G9") (pintype "passive"))
      (node (ref "D1") (pin "T4") (pinfunction "VDD1_T4") (pintype "passive"))
      (node (ref "D1") (pin "T9") (pinfunction "VDD1_T9") (pintype "passive"))
      (node (ref "D1") (pin "U1") (pinfunction "VDD1_U1") (pintype "passive"))
      (node (ref "D1") (pin "U12") (pinfunction "VDD1_U12") (pintype "passive"))
      (node (ref "R6") (pin "2") (pinfunction "2_2") (pintype "passive"))
    )
    (net (code "81") (name "VDD2_DDR_S3") (class "Default")
      (node (ref "C30") (pin "2") (pinfunction "2_2") (pintype "passive"))
      (node (ref "C31") (pin "2") (pinfunction "2_2") (pintype "passive"))
      (node (ref "C33") (pin "2") (pinfunction "2_2") (pintype "passive"))
      (node (ref "C34") (pin "2") (pinfunction "2_2") (pintype "passive"))
      (node (ref "C35") (pin "2") (pinfunction "2_2") (pintype "passive"))
      (node (ref "C36") (pin "2") (pinfunction "2_2") (pintype "passive"))
      (node (ref "C37") (pin "2") (pinfunction "2_2") (pintype "passive"))
      (node (ref "C38") (pin "2") (pinfunction "2_2") (pintype "passive"))
      (node (ref "C39") (pin "2") (pinfunction "2_2") (pintype "passive"))
      (node (ref "C40") (pin "2") (pinfunction "2_2") (pintype "passive"))
      (node (ref "C41") (pin "2") (pinfunction "2_2") (pintype "passive"))
      (node (ref "C42") (pin "2") (pinfunction "2_2") (pintype "passive"))
      (node (ref "C43") (pin "2") (pinfunction "2_2") (pintype "passive"))
      (node (ref "D1") (pin "A4") (pinfunction "VDD2_A4") (pintype "passive"))
      (node (ref "D1") (pin "A9") (pinfunction "VDD2_A9") (pintype "passive"))
      (node (ref "D1") (pin "AB4") (pinfunction "VDD2_AB4") (pintype "passive"))
      (node (ref "D1") (pin "AB9") (pinfunction "VDD2_AB9") (pintype "passive"))
      (node (ref "D1") (pin "F5") (pinfunction "VDD2_F5") (pintype "passive"))
      (node (ref "D1") (pin "F8") (pinfunction "VDD2_F8") (pintype "passive"))
      (node (ref "D1") (pin "G2") (pinfunction "ODT_CA_A_G2") (pintype "passive"))
      (node (ref "D1") (pin "H1") (pinfunction "VDD2_H1") (pintype "passive"))
      (node (ref "D1") (pin "H12") (pinfunction "VDD2_H12") (pintype "passive"))
      (node (ref "D1") (pin "H5") (pinfunction "VDD2_H5") (pintype "passive"))
      (node (ref "D1") (pin "H8") (pinfunction "VDD2_H8") (pintype "passive"))
      (node (ref "D1") (pin "K1") (pinfunction "VDD2_K1") (pintype "passive"))
      (node (ref "D1") (pin "K10") (pinfunction "VDD2_K10") (pintype "passive"))
      (node (ref "D1") (pin "K12") (pinfunction "VDD2_K12") (pintype "passive"))
      (node (ref "D1") (pin "K3") (pinfunction "VDD2_K3") (pintype "passive"))
      (node (ref "D1") (pin "N1") (pinfunction "VDD2_N1") (pintype "passive"))
      (node (ref "D1") (pin "N10") (pinfunction "VDD2_N10") (pintype "passive"))
      (node (ref "D1") (pin "N12") (pinfunction "VDD2_N12") (pintype "passive"))
      (node (ref "D1") (pin "N3") (pinfunction "VDD2_N3") (pintype "passive"))
      (node (ref "D1") (pin "R1") (pinfunction "VDD2_R1") (pintype "passive"))
      (node (ref "D1") (pin "R12") (pinfunction "VDD2_R12") (pintype "passive"))
      (node (ref "D1") (pin "R5") (pinfunction "VDD2_R5") (pintype "passive"))
      (node (ref "D1") (pin "R8") (pinfunction "VDD2_R8") (pintype "passive"))
      (node (ref "D1") (pin "T2") (pinfunction "ODT_CA_B_T2") (pintype "passive"))
      (node (ref "D1") (pin "U5") (pinfunction "VDD2_U5") (pintype "passive"))
      (node (ref "D1") (pin "U8") (pinfunction "VDD2_U8") (pintype "passive"))
      (node (ref "R488") (pin "1") (pinfunction "1_1") (pintype "passive"))
      (node (ref "R5") (pin "1") (pinfunction "1_1") (pintype "passive"))
    )
    (net (code "82") (name "VDDQ_DDR_CKE_S3") (class "Default")
      (node (ref "R488") (pin "2") (pinfunction "2_2") (pintype "passive"))
    )
    (net (code "83") (name "VDDQ_DDR_S0") (class "Default")
      (node (ref "R4") (pin "1") (pinfunction "1_1") (pintype "passive"))
    )
    (net (code "84") (name "VDDQ_DRAM_S0") (class "Default")
      (node (ref "C11") (pin "2") (pinfunction "2_2") (pintype "passive"))
      (node (ref "C12") (pin "2") (pinfunction "2_2") (pintype "passive"))
      (node (ref "C14") (pin "2") (pinfunction "2_2") (pintype "passive"))
      (node (ref "C15") (pin "2") (pinfunction "2_2") (pintype "passive"))
      (node (ref "C16") (pin "2") (pinfunction "2_2") (pintype "passive"))
      (node (ref "C18") (pin "2") (pinfunction "2_2") (pintype "passive"))
      (node (ref "C19") (pin "2") (pinfunction "2_2") (pintype "passive"))
      (node (ref "C20") (pin "2") (pinfunction "2_2") (pintype "passive"))
      (node (ref "C21") (pin "2") (pinfunction "2_2") (pintype "passive"))
      (node (ref "C22") (pin "2") (pinfunction "2_2") (pintype "passive"))
      (node (ref "C25") (pin "2") (pinfunction "2_2") (pintype "passive"))
      (node (ref "C26") (pin "2") (pinfunction "2_2") (pintype "passive"))
      (node (ref "C27") (pin "2") (pinfunction "2_2") (pintype "passive"))
      (node (ref "C28") (pin "2") (pinfunction "2_2") (pintype "passive"))
      (node (ref "C29") (pin "2") (pinfunction "2_2") (pintype "passive"))
      (node (ref "D1") (pin "AA10") (pinfunction "VDDQ_AA10") (pintype "passive"))
      (node (ref "D1") (pin "AA3") (pinfunction "VDDQ_AA3") (pintype "passive"))
      (node (ref "D1") (pin "AA5") (pinfunction "VDDQ_AA5") (pintype "passive"))
      (node (ref "D1") (pin "AA8") (pinfunction "VDDQ_AA8") (pintype "passive"))
      (node (ref "D1") (pin "B10") (pinfunction "VDDQ_B10") (pintype "passive"))
      (node (ref "D1") (pin "B3") (pinfunction "VDDQ_B3") (pintype "passive"))
      (node (ref "D1") (pin "B5") (pinfunction "VDDQ_B5") (pintype "passive"))
      (node (ref "D1") (pin "B8") (pinfunction "VDDQ_B8") (pintype "passive"))
      (node (ref "D1") (pin "D1") (pinfunction "VDDQ_D1") (pintype "passive"))
      (node (ref "D1") (pin "D12") (pinfunction "VDDQ_D12") (pintype "passive"))
      (node (ref "D1") (pin "D5") (pinfunction "VDDQ_D5") (pintype "passive"))
      (node (ref "D1") (pin "D8") (pinfunction "VDDQ_D8") (pintype "passive"))
      (node (ref "D1") (pin "F10") (pinfunction "VDDQ_F10") (pintype "passive"))
      (node (ref "D1") (pin "F3") (pinfunction "VDDQ_F3") (pintype "passive"))
      (node (ref "D1") (pin "U10") (pinfunction "VDDQ_U10") (pintype "passive"))
      (node (ref "D1") (pin "U3") (pinfunction "VDDQ_U3") (pintype "passive"))
      (node (ref "D1") (pin "W1") (pinfunction "VDDQ_W1") (pintype "passive"))
      (node (ref "D1") (pin "W12") (pinfunction "VDDQ_W12") (pintype "passive"))
      (node (ref "D1") (pin "W5") (pinfunction "VDDQ_W5") (pintype "passive"))
      (node (ref "D1") (pin "W8") (pinfunction "VDDQ_W8") (pintype "passive"))
      (node (ref "R1") (pin "1") (pinfunction "1_1") (pintype "passive"))
      (node (ref "R3") (pin "1") (pinfunction "1_1") (pintype "passive"))
      (node (ref "R4") (pin "2") (pinfunction "2_2") (pintype "passive"))
      (node (ref "R5") (pin "2") (pinfunction "2_2") (pintype "passive"))
    )
    (net (code "85") (name "unconnected-(D1B-NC-PadG11)") (class "Default")
      (node (ref "D1") (pin "G11") (pinfunction "NC_G11") (pintype "passive+no_connect"))
    )
    (net (code "86") (name "unconnected-(D1B-NC-PadK5)") (class "Default")
      (node (ref "D1") (pin "K5") (pinfunction "NC_K5") (pintype "passive+no_connect"))
    )
    (net (code "87") (name "unconnected-(D1B-NC-PadK8)") (class "Default")
      (node (ref "D1") (pin "K8") (pinfunction "NC_K8") (pintype "passive+no_connect"))
    )
    (net (code "88") (name "unconnected-(D1B-NC-PadN5)") (class "Default")
      (node (ref "D1") (pin "N5") (pinfunction "NC_N5") (pintype "passive+no_connect"))
    )
    (net (code "89") (name "unconnected-(D1B-NC-PadN8)") (class "Default")
      (node (ref "D1") (pin "N8") (pinfunction "NC_N8") (pintype "passive+no_connect"))
    )
    (net (code "90") (name "unconnected-(D1C-DNU-PadA1)") (class "Default")
      (node (ref "D1") (pin "A1") (pinfunction "DNU_A1") (pintype "passive+no_connect"))
    )
    (net (code "91") (name "unconnected-(D1C-DNU-PadA2)") (class "Default")
      (node (ref "D1") (pin "A2") (pinfunction "DNU_A2") (pintype "passive+no_connect"))
    )
    (net (code "92") (name "unconnected-(D1C-DNU-PadA11)") (class "Default")
      (node (ref "D1") (pin "A11") (pinfunction "DNU_A11") (pintype "passive+no_connect"))
    )
    (net (code "93") (name "unconnected-(D1C-DNU-PadA12)") (class "Default")
      (node (ref "D1") (pin "A12") (pinfunction "DNU_A12") (pintype "passive+no_connect"))
    )
    (net (code "94") (name "unconnected-(D1C-DNU-PadAA1)") (class "Default")
      (node (ref "D1") (pin "AA1") (pinfunction "DNU_AA1") (pintype "passive+no_connect"))
    )
    (net (code "95") (name "unconnected-(D1C-DNU-PadAA12)") (class "Default")
      (node (ref "D1") (pin "AA12") (pinfunction "DNU_AA12") (pintype "passive+no_connect"))
    )
    (net (code "96") (name "unconnected-(D1C-DNU-PadAB1)") (class "Default")
      (node (ref "D1") (pin "AB1") (pinfunction "DNU_AB1") (pintype "passive+no_connect"))
    )
    (net (code "97") (name "unconnected-(D1C-DNU-PadAB2)") (class "Default")
      (node (ref "D1") (pin "AB2") (pinfunction "DNU_AB2") (pintype "passive+no_connect"))
    )
    (net (code "98") (name "unconnected-(D1C-DNU-PadAB11)") (class "Default")
      (node (ref "D1") (pin "AB11") (pinfunction "DNU_AB11") (pintype "passive+no_connect"))
    )
    (net (code "99") (name "unconnected-(D1C-DNU-PadAB12)") (class "Default")
      (node (ref "D1") (pin "AB12") (pinfunction "DNU_AB12") (pintype "passive+no_connect"))
    )
    (net (code "100") (name "unconnected-(D1C-DNU-PadB1)") (class "Default")
      (node (ref "D1") (pin "B1") (pinfunction "DNU_B1") (pintype "passive+no_connect"))
    )
    (net (code "101") (name "unconnected-(D1C-DNU-PadB12)") (class "Default")
      (node (ref "D1") (pin "B12") (pinfunction "DNU_B12") (pintype "passive+no_connect"))
    )
  )
)
